# PAPI_M1_Sensor.net
KiCad netlist of a schematic drawn in Altium Designer
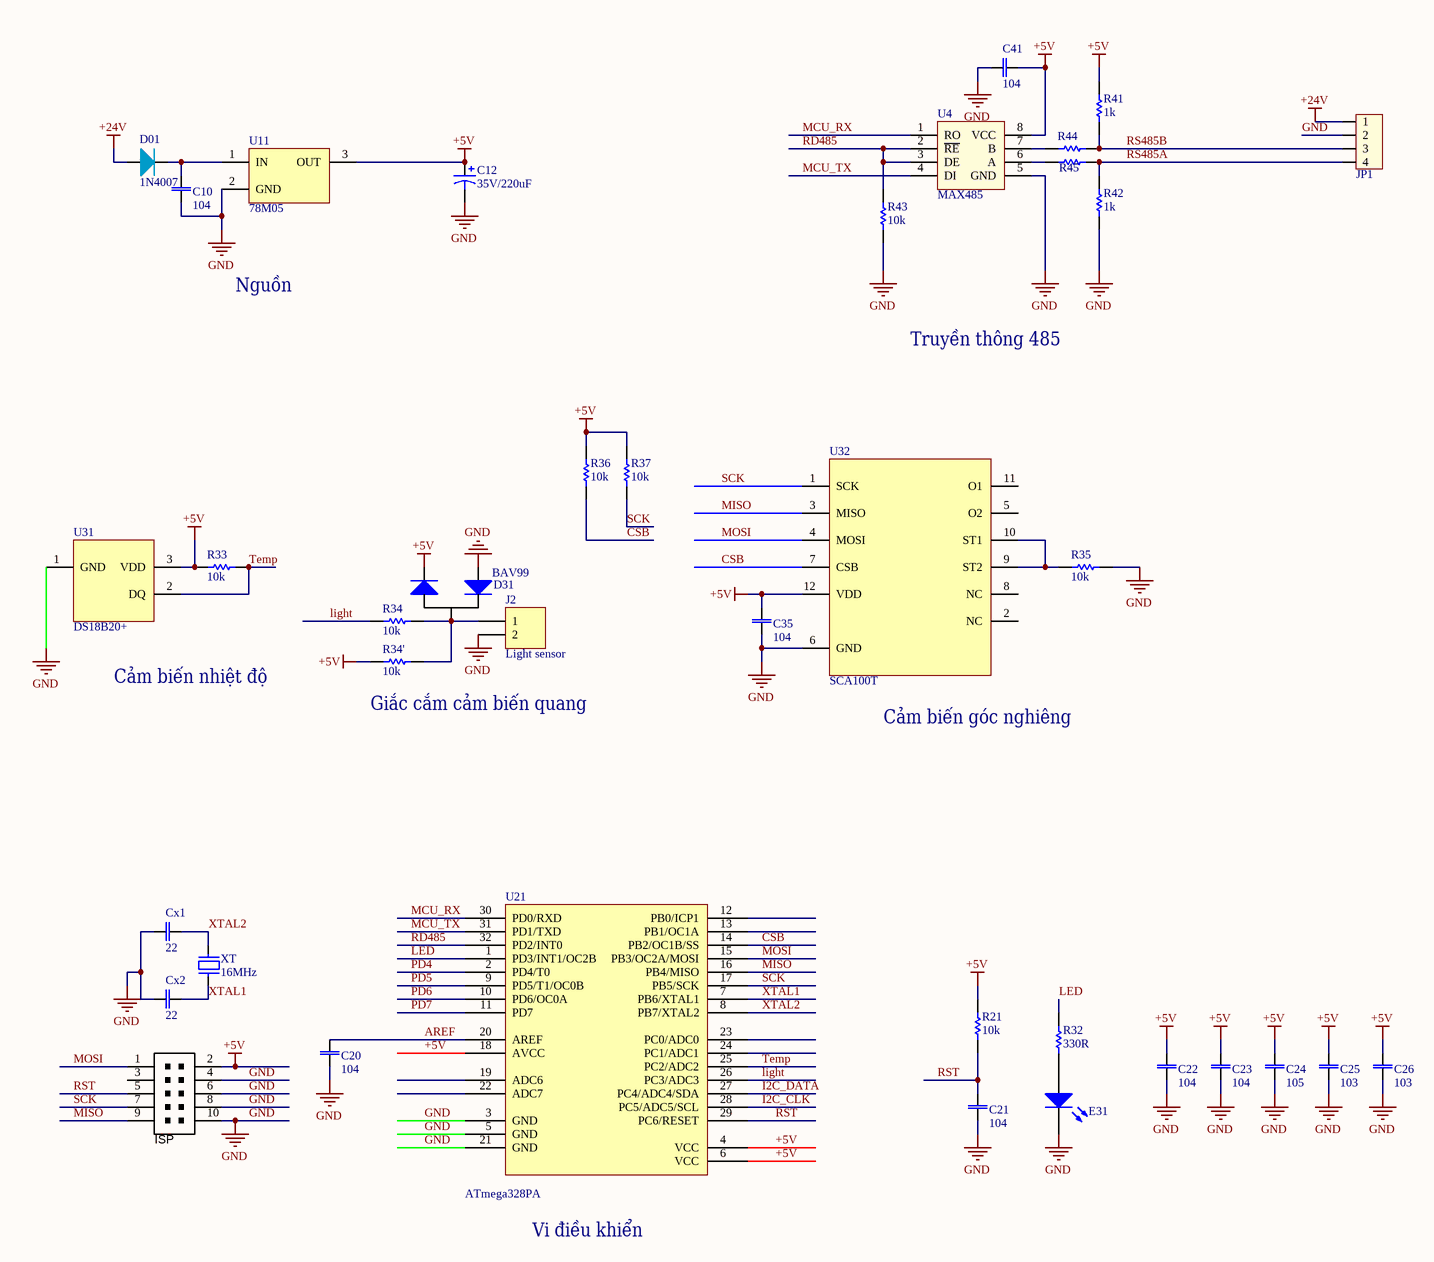
[diagram p0: PAPI_M1_Sensor.SchDoc]

(export (version "E")
  (design (tool "Eeschema 10.0.6"))
  (components
    (comp (ref "C10")
      (value "104")
      (footprint "PBL - SMD Packages:CAPC2012N_F")
      (description "Capacitor non polarized")
      (fields (field (name "Comment") "Tụ điện dán 0805104"))
      (libsource (lib "Tuan") (part "CAP NP"))
    )
    (comp (ref "C12")
      (value "35V/220uF")
      (footprint "CAPE3.5-5.0MM_Rad_10x14mm")
      (fields (field (name "Comment") "Cap"))
      (libsource (lib "Tuan") (part "Cap"))
    )
    (comp (ref "C20")
      (value "104")
      (footprint "PBL - SMD Packages:CAPC2012N_F")
      (description "Capacitor non polarized")
      (fields (field (name "Comment") "Tụ điện dán 0603104"))
      (libsource (lib "Tuan") (part "CAP NP"))
    )
    (comp (ref "C21")
      (value "104")
      (footprint "PBL - SMD Packages:CAPC2012N_F")
      (description "Capacitor non polarized")
      (fields (field (name "Comment") "Tụ điện dán 0603104"))
      (libsource (lib "Tuan") (part "CAP NP"))
    )
    (comp (ref "C22")
      (value "104")
      (footprint "PBL - SMD Packages:CAPC2012N_F")
      (description "Capacitor non polarized")
      (fields (field (name "Comment") "Tụ điện dán 0805104"))
      (libsource (lib "Tuan") (part "CAP NP"))
    )
    (comp (ref "C23")
      (value "104")
      (footprint "PBL - SMD Packages:CAPC2012N_F")
      (description "Capacitor non polarized")
      (fields (field (name "Comment") "Tụ điện dán 0805104"))
      (libsource (lib "Tuan") (part "CAP NP"))
    )
    (comp (ref "C24")
      (value "105")
      (footprint "PBL - SMD Packages:CAPC2012N_F")
      (description "Capacitor non polarized")
      (fields (field (name "Comment") "Tụ điện dán 0805105"))
      (libsource (lib "Tuan") (part "CAP NP"))
    )
    (comp (ref "C25")
      (value "103")
      (footprint "PBL - SMD Packages:CAPC2012N_F")
      (description "Capacitor non polarized")
      (fields (field (name "Comment") "Tụ điện dán 0805103"))
      (libsource (lib "Tuan") (part "CAP NP"))
    )
    (comp (ref "C26")
      (value "103")
      (footprint "PBL - SMD Packages:CAPC2012N_F")
      (description "Capacitor non polarized")
      (fields (field (name "Comment") "Tụ điện dán 0805103"))
      (libsource (lib "Tuan") (part "CAP NP"))
    )
    (comp (ref "C35")
      (value "104")
      (footprint "PBL - SMD Packages:CAPC2012N_F")
      (description "Capacitor non polarized")
      (fields (field (name "Comment") "Tụ điện dán 0805104"))
      (libsource (lib "Tuan") (part "CAP NP"))
    )
    (comp (ref "C41")
      (value "104")
      (footprint "PBL - SMD Packages:CAPC2012N_F")
      (description "Capacitor non polarized")
      (fields (field (name "Comment") "Tụ điện dán 0805104"))
      (libsource (lib "Tuan") (part "CAP NP"))
    )
    (comp (ref "Cx1")
      (value "22")
      (footprint "PBL - SMD Packages:CAPC2012N_F")
      (description "Capacitor non polarized")
      (fields (field (name "Comment") "Tụ điện dán 060322"))
      (libsource (lib "Tuan") (part "CAP NP"))
    )
    (comp (ref "Cx2")
      (value "22")
      (footprint "PBL - SMD Packages:CAPC2012N_F")
      (description "Capacitor non polarized")
      (fields (field (name "Comment") "Tụ điện dán 060322"))
      (libsource (lib "Tuan") (part "CAP NP"))
    )
    (comp (ref "D01")
      (value "Đi ốt cắm1N4007")
      (footprint "swatpcblib:DO-41")
      (fields (field (name "VL1") "1N4007"))
      (libsource (lib "swatpcblib") (part "Diode"))
    )
    (comp (ref "D31")
      (value "BAV99")
      (footprint "SOT323")
      (description "Diode Array 1 Pair Series Connection Standard 70V 215mA (DC) Surface Mount SC-70, SOT-323")
      (libsource (lib "Tuan") (part "BAV99W"))
    )
    (comp (ref "E31") (value "Led") (footprint "LED 5mm Green") (libsource (lib "Tuan") (part "Led")))
    (comp (ref "ISP")
      (value "Giắc đôi 5x2 chân 2.54mm")
      (footprint "10P_PCB_HEADER_BRD_MNT")
      (description "Header THD 10 POS Double-row 2.54mm pitch")
      (libsource (lib "PBL - Connectors") (part "CONN_HEADER_2x5P_0.100in_Male"))
    )
    (comp (ref "J2")
      (value "Light sensor")
      (footprint "heromap:HDR1X2")
      (description "Header, 2-Pin")
      (fields (field (name "PUBLISHER") "Altium Limited"))
      (libsource (lib "heromap") (part "Header 2"))
    )
    (comp (ref "JP1")
      (value "JP4")
      (footprint "heromap:CON4")
      (description "Connector 4")
      (libsource (lib "heromap") (part "Con4"))
    )
    (comp (ref "R21")
      (value "10k")
      (footprint "PBL - SMD Packages:RESC2012N_F")
      (description "Resistor")
      (fields (field (name "Comment") "Điện trở dán 060310k"))
      (libsource (lib "Tuan") (part "Res"))
    )
    (comp (ref "R32")
      (value "330R")
      (footprint "PBL - SMD Packages:RESC2012N_F")
      (description "Resistor")
      (fields (field (name "Comment") "Điện trở dán 0603330R"))
      (libsource (lib "Tuan") (part "Res"))
    )
    (comp (ref "R33")
      (value "10k")
      (footprint "RESC2012N_F")
      (fields (field (name "Comment") "Res_10k_0603"))
      (libsource (lib "Tuan") (part "Res"))
    )
    (comp (ref "R34")
      (value "10k")
      (footprint "RESC2012N_F")
      (fields (field (name "Comment") "Res_10k_0603"))
      (libsource (lib "Tuan") (part "Res"))
    )
    (comp (ref "R34'")
      (value "10k")
      (footprint "RESC2012N_F")
      (fields (field (name "Comment") "Res_10k_0603"))
      (libsource (lib "Tuan") (part "Res"))
    )
    (comp (ref "R35")
      (value "10k")
      (footprint "PBL - SMD Packages:RESC2012N_F")
      (description "Resistor")
      (fields (field (name "Comment") "Điện trở dán 060310k"))
      (libsource (lib "Tuan") (part "Res"))
    )
    (comp (ref "R36")
      (value "10k")
      (footprint "PBL - SMD Packages:RESC2012N_F")
      (description "Resistor")
      (fields (field (name "Comment") "Điện trở dán 060310k"))
      (libsource (lib "Tuan") (part "Res"))
    )
    (comp (ref "R37")
      (value "10k")
      (footprint "PBL - SMD Packages:RESC2012N_F")
      (description "Resistor")
      (fields (field (name "Comment") "Điện trở dán 060310k"))
      (libsource (lib "Tuan") (part "Res"))
    )
    (comp (ref "R41")
      (value "1k")
      (footprint "RESC2012N_F")
      (fields (field (name "Comment") "Res_1k_0603"))
      (libsource (lib "Tuan") (part "Res"))
    )
    (comp (ref "R42")
      (value "1k")
      (footprint "RESC2012N_F")
      (fields (field (name "Comment") "Res_1k_0603"))
      (libsource (lib "Tuan") (part "Res"))
    )
    (comp (ref "R43")
      (value "10k")
      (footprint "RESC2012N_F")
      (fields (field (name "Comment") "Res_10k_0603"))
      (libsource (lib "Tuan") (part "Res"))
    )
    (comp (ref "R44") (value "Res_10R_0805") (footprint "RESC2012N_F") (libsource (lib "Tuan") (part "Res")))
    (comp (ref "R45") (value "Res_10R_0805") (footprint "RESC2012N_F") (libsource (lib "Tuan") (part "Res")))
    (comp (ref "U4")
      (value "MAX485")
      (footprint "SOIC 8")
      (description "RS232 - RS485 (Same sn75176)")
      (libsource (lib "heromap") (part "MAX485"))
    )
    (comp (ref "U11")
      (value "78M05")
      (footprint "TO252 D-PAK")
      (description "Linear Voltage Regulators 5V 500mA Positive")
      (libsource (lib "Tuan") (part "LM78xx"))
    )
    (comp (ref "U21")
      (value "ATmega328PA")
      (footprint "TQFP32")
      (description "ATmega48/168/328")
      (libsource (lib "Tuan") (part "ATmega48/168/328"))
    )
    (comp (ref "U31")
      (value "DS18B20+")
      (footprint "QTO-92")
      (description "SENSOR TEMPERATURE 1-WIRE TO92-3")
      (fields (field (name "DIGI-KEY PART NUMBER") "DS18B20+-ND"))
      (libsource (lib "Tuan") (part "DS18B20"))
    )
    (comp (ref "U32")
      (value "SCA100T")
      (footprint "SCA100T")
      (description "Accelerometer X, Y Axis ±12g 400Hz 12-SMD")
      (libsource (lib "Tuan") (part "SCA100T"))
    )
    (comp (ref "XT") (value "16MHz") (footprint "XT2") (libsource (lib "Tuan") (part "Crystal")))
  )
  (nets
    (net (code "1") (name "+5V") (class "Default")
      (node (ref "C12") (pin "1") (pinfunction "1_1") (pintype "passive"))
      (node (ref "C22") (pin "2") (pinfunction "2_2") (pintype "passive"))
      (node (ref "C23") (pin "2") (pinfunction "2_2") (pintype "passive"))
      (node (ref "C24") (pin "2") (pinfunction "2_2") (pintype "passive"))
      (node (ref "C25") (pin "2") (pinfunction "2_2") (pintype "passive"))
      (node (ref "C26") (pin "2") (pinfunction "2_2") (pintype "passive"))
      (node (ref "C35") (pin "1") (pinfunction "1_1") (pintype "passive"))
      (node (ref "C41") (pin "1") (pinfunction "1_1") (pintype "passive"))
      (node (ref "D31") (pin "2") (pinfunction "K_2") (pintype "passive"))
      (node (ref "ISP") (pin "2") (pinfunction "2_2") (pintype "passive"))
      (node (ref "R21") (pin "2") (pinfunction "2_2") (pintype "passive"))
      (node (ref "R33") (pin "2") (pinfunction "2_2") (pintype "passive"))
      (node (ref "R34'") (pin "2") (pinfunction "2_2") (pintype "passive"))
      (node (ref "R36") (pin "1") (pinfunction "1_1") (pintype "passive"))
      (node (ref "R37") (pin "1") (pinfunction "1_1") (pintype "passive"))
      (node (ref "R41") (pin "2") (pinfunction "2_2") (pintype "passive"))
      (node (ref "U11") (pin "3") (pinfunction "OUT_3") (pintype "passive"))
      (node (ref "U21") (pin "18") (pinfunction "AVCC_18") (pintype "passive"))
      (node (ref "U21") (pin "4") (pinfunction "VCC_4") (pintype "passive"))
      (node (ref "U21") (pin "6") (pinfunction "VCC_6") (pintype "passive"))
      (node (ref "U31") (pin "3") (pinfunction "VDD_3") (pintype "passive"))
      (node (ref "U32") (pin "12") (pinfunction "VDD_12") (pintype "passive"))
      (node (ref "U4") (pin "8") (pinfunction "VCC_8") (pintype "passive"))
    )
    (net (code "2") (name "+24V") (class "Default")
      (node (ref "D01") (pin "A") (pinfunction "A_A") (pintype "passive"))
      (node (ref "JP1") (pin "1") (pinfunction "1_1") (pintype "passive"))
    )
    (net (code "3") (name "/AREF") (class "Default")
      (node (ref "C20") (pin "2") (pinfunction "2_2") (pintype "passive"))
      (node (ref "U21") (pin "20") (pinfunction "AREF_20") (pintype "passive"))
    )
    (net (code "4") (name "/CSB") (class "Default")
      (node (ref "R36") (pin "2") (pinfunction "2_2") (pintype "passive"))
      (node (ref "U21") (pin "14") (pinfunction "PB2/OC1B/SS_14") (pintype "passive"))
      (node (ref "U32") (pin "7") (pinfunction "CSB_7") (pintype "passive"))
    )
    (net (code "5") (name "/I2C_CLK") (class "Default")
      (node (ref "U21") (pin "28") (pinfunction "PC5/ADC5/SCL_28") (pintype "passive"))
    )
    (net (code "6") (name "/I2C_DATA") (class "Default")
      (node (ref "U21") (pin "27") (pinfunction "PC4/ADC4/SDA_27") (pintype "passive"))
    )
    (net (code "7") (name "/LED") (class "Default")
      (node (ref "R32") (pin "1") (pinfunction "1_1") (pintype "passive"))
      (node (ref "U21") (pin "1") (pinfunction "PD3/INT1/OC2B_1") (pintype "passive"))
    )
    (net (code "8") (name "/MCU_RX") (class "Default")
      (node (ref "U21") (pin "30") (pinfunction "PD0/RXD_30") (pintype "passive"))
      (node (ref "U4") (pin "1") (pinfunction "RO_1") (pintype "passive"))
    )
    (net (code "9") (name "/MCU_TX") (class "Default")
      (node (ref "U21") (pin "31") (pinfunction "PD1/TXD_31") (pintype "passive"))
      (node (ref "U4") (pin "4") (pinfunction "DI_4") (pintype "passive"))
    )
    (net (code "10") (name "/MISO") (class "Default")
      (node (ref "ISP") (pin "9") (pinfunction "9_9") (pintype "passive"))
      (node (ref "U21") (pin "16") (pinfunction "PB4/MISO_16") (pintype "passive"))
      (node (ref "U32") (pin "3") (pinfunction "MISO_3") (pintype "passive"))
    )
    (net (code "11") (name "/MOSI") (class "Default")
      (node (ref "ISP") (pin "1") (pinfunction "1_1") (pintype "passive"))
      (node (ref "U21") (pin "15") (pinfunction "PB3/OC2A/MOSI_15") (pintype "passive"))
      (node (ref "U32") (pin "4") (pinfunction "MOSI_4") (pintype "passive"))
    )
    (net (code "12") (name "/PD4") (class "Default")
      (node (ref "U21") (pin "2") (pinfunction "PD4/T0_2") (pintype "passive"))
    )
    (net (code "13") (name "/PD5") (class "Default")
      (node (ref "U21") (pin "9") (pinfunction "PD5/T1/OC0B_9") (pintype "passive"))
    )
    (net (code "14") (name "/PD6") (class "Default")
      (node (ref "U21") (pin "10") (pinfunction "PD6/OC0A_10") (pintype "passive"))
    )
    (net (code "15") (name "/PD7") (class "Default")
      (node (ref "U21") (pin "11") (pinfunction "PD7_11") (pintype "passive"))
    )
    (net (code "16") (name "/RD485") (class "Default")
      (node (ref "R43") (pin "2") (pinfunction "2_2") (pintype "passive"))
      (node (ref "U21") (pin "32") (pinfunction "PD2/INT0_32") (pintype "passive"))
      (node (ref "U4") (pin "2") (pinfunction "~{RE}_2") (pintype "passive"))
      (node (ref "U4") (pin "3") (pinfunction "DE_3") (pintype "passive"))
    )
    (net (code "17") (name "/RS485A") (class "Default")
      (node (ref "JP1") (pin "4") (pinfunction "4_4") (pintype "passive"))
      (node (ref "R42") (pin "2") (pinfunction "2_2") (pintype "passive"))
      (node (ref "R45") (pin "2") (pinfunction "2_2") (pintype "passive"))
    )
    (net (code "18") (name "/RS485B") (class "Default")
      (node (ref "JP1") (pin "3") (pinfunction "3_3") (pintype "passive"))
      (node (ref "R41") (pin "1") (pinfunction "1_1") (pintype "passive"))
      (node (ref "R44") (pin "2") (pinfunction "2_2") (pintype "passive"))
    )
    (net (code "19") (name "/RST") (class "Default")
      (node (ref "C21") (pin "2") (pinfunction "2_2") (pintype "passive"))
      (node (ref "ISP") (pin "5") (pinfunction "5_5") (pintype "passive"))
      (node (ref "R21") (pin "1") (pinfunction "1_1") (pintype "passive"))
      (node (ref "U21") (pin "29") (pinfunction "PC6/RESET_29") (pintype "passive"))
    )
    (net (code "20") (name "/SCK") (class "Default")
      (node (ref "ISP") (pin "7") (pinfunction "7_7") (pintype "passive"))
      (node (ref "R37") (pin "2") (pinfunction "2_2") (pintype "passive"))
      (node (ref "U21") (pin "17") (pinfunction "PB5/SCK_17") (pintype "passive"))
      (node (ref "U32") (pin "1") (pinfunction "SCK_1") (pintype "passive"))
    )
    (net (code "21") (name "/Temp") (class "Default")
      (node (ref "R33") (pin "1") (pinfunction "1_1") (pintype "passive"))
      (node (ref "U21") (pin "25") (pinfunction "PC2/ADC2_25") (pintype "passive"))
      (node (ref "U31") (pin "2") (pinfunction "DQ_2") (pintype "passive"))
    )
    (net (code "22") (name "/XTAL1") (class "Default")
      (node (ref "Cx2") (pin "1") (pinfunction "1_1") (pintype "passive"))
      (node (ref "U21") (pin "7") (pinfunction "PB6/XTAL1_7") (pintype "passive"))
      (node (ref "XT") (pin "1") (pinfunction "1_1") (pintype "passive"))
    )
    (net (code "23") (name "/XTAL2") (class "Default")
      (node (ref "Cx1") (pin "1") (pinfunction "1_1") (pintype "passive"))
      (node (ref "U21") (pin "8") (pinfunction "PB7/XTAL2_8") (pintype "passive"))
      (node (ref "XT") (pin "2") (pinfunction "2_2") (pintype "passive"))
    )
    (net (code "24") (name "/light") (class "Default")
      (node (ref "R34") (pin "1") (pinfunction "1_1") (pintype "passive"))
      (node (ref "U21") (pin "26") (pinfunction "PC3/ADC3_26") (pintype "passive"))
    )
    (net (code "25") (name "GND") (class "Default")
      (node (ref "C10") (pin "1") (pinfunction "1_1") (pintype "passive"))
      (node (ref "C12") (pin "2") (pinfunction "2_2") (pintype "passive"))
      (node (ref "C20") (pin "1") (pinfunction "1_1") (pintype "passive"))
      (node (ref "C21") (pin "1") (pinfunction "1_1") (pintype "passive"))
      (node (ref "C22") (pin "1") (pinfunction "1_1") (pintype "passive"))
      (node (ref "C23") (pin "1") (pinfunction "1_1") (pintype "passive"))
      (node (ref "C24") (pin "1") (pinfunction "1_1") (pintype "passive"))
      (node (ref "C25") (pin "1") (pinfunction "1_1") (pintype "passive"))
      (node (ref "C26") (pin "1") (pinfunction "1_1") (pintype "passive"))
      (node (ref "C35") (pin "2") (pinfunction "2_2") (pintype "passive"))
      (node (ref "C41") (pin "2") (pinfunction "2_2") (pintype "passive"))
      (node (ref "Cx1") (pin "2") (pinfunction "2_2") (pintype "passive"))
      (node (ref "Cx2") (pin "2") (pinfunction "2_2") (pintype "passive"))
      (node (ref "D31") (pin "1") (pinfunction "A_1") (pintype "passive"))
      (node (ref "E31") (pin "2") (pinfunction "K_2") (pintype "passive"))
      (node (ref "ISP") (pin "10") (pinfunction "10_10") (pintype "passive"))
      (node (ref "ISP") (pin "4") (pinfunction "4_4") (pintype "passive"))
      (node (ref "ISP") (pin "6") (pinfunction "6_6") (pintype "passive"))
      (node (ref "ISP") (pin "8") (pinfunction "8_8") (pintype "passive"))
      (node (ref "J2") (pin "2") (pinfunction "2_2") (pintype "passive"))
      (node (ref "JP1") (pin "2") (pinfunction "2_2") (pintype "passive"))
      (node (ref "R35") (pin "1") (pinfunction "1_1") (pintype "passive"))
      (node (ref "R42") (pin "1") (pinfunction "1_1") (pintype "passive"))
      (node (ref "R43") (pin "1") (pinfunction "1_1") (pintype "passive"))
      (node (ref "U11") (pin "2") (pinfunction "GND_2") (pintype "passive"))
      (node (ref "U21") (pin "21") (pinfunction "GND_21") (pintype "power_in"))
      (node (ref "U21") (pin "3") (pinfunction "GND_3") (pintype "power_in"))
      (node (ref "U21") (pin "5") (pinfunction "GND_5") (pintype "power_in"))
      (node (ref "U31") (pin "1") (pinfunction "GND_1") (pintype "passive"))
      (node (ref "U32") (pin "6") (pinfunction "GND_6") (pintype "passive"))
      (node (ref "U4") (pin "5") (pinfunction "GND_5") (pintype "passive"))
    )
    (net (code "26") (name "Net-(D31-AK)") (class "Default")
      (node (ref "D31") (pin "3") (pinfunction "AK_3") (pintype "passive"))
      (node (ref "J2") (pin "1") (pinfunction "1_1") (pintype "passive"))
      (node (ref "R34") (pin "2") (pinfunction "2_2") (pintype "passive"))
      (node (ref "R34'") (pin "1") (pinfunction "1_1") (pintype "passive"))
    )
    (net (code "27") (name "Net-(E31-A)") (class "Default")
      (node (ref "E31") (pin "1") (pinfunction "A_1") (pintype "passive"))
      (node (ref "R32") (pin "2") (pinfunction "2_2") (pintype "passive"))
    )
    (net (code "28") (name "Net-(U4-A)") (class "Default")
      (node (ref "R45") (pin "1") (pinfunction "1_1") (pintype "passive"))
      (node (ref "U4") (pin "6") (pinfunction "A_6") (pintype "passive"))
    )
    (net (code "29") (name "Net-(U4-B)") (class "Default")
      (node (ref "R44") (pin "1") (pinfunction "1_1") (pintype "passive"))
      (node (ref "U4") (pin "7") (pinfunction "B_7") (pintype "passive"))
    )
    (net (code "30") (name "Net-(U11-IN)") (class "Default")
      (node (ref "C10") (pin "2") (pinfunction "2_2") (pintype "passive"))
      (node (ref "D01") (pin "K") (pinfunction "K_K") (pintype "passive"))
      (node (ref "U11") (pin "1") (pinfunction "IN_1") (pintype "passive"))
    )
    (net (code "31") (name "Net-(U32-ST1)") (class "Default")
      (node (ref "R35") (pin "2") (pinfunction "2_2") (pintype "passive"))
      (node (ref "U32") (pin "10") (pinfunction "ST1_10") (pintype "passive"))
      (node (ref "U32") (pin "9") (pinfunction "ST2_9") (pintype "passive"))
    )
    (net (code "32") (name "unconnected-(ISP-Pad3)") (class "Default")
      (node (ref "ISP") (pin "3") (pinfunction "3_3") (pintype "passive"))
    )
    (net (code "33") (name "unconnected-(U21-ADC6-Pad19)") (class "Default")
      (node (ref "U21") (pin "19") (pinfunction "ADC6_19") (pintype "passive"))
    )
    (net (code "34") (name "unconnected-(U21-ADC7-Pad22)") (class "Default")
      (node (ref "U21") (pin "22") (pinfunction "ADC7_22") (pintype "passive"))
    )
    (net (code "35") (name "unconnected-(U21-PB0{slash}ICP1-Pad12)") (class "Default")
      (node (ref "U21") (pin "12") (pinfunction "PB0/ICP1_12") (pintype "passive"))
    )
    (net (code "36") (name "unconnected-(U21-PB1{slash}OC1A-Pad13)") (class "Default")
      (node (ref "U21") (pin "13") (pinfunction "PB1/OC1A_13") (pintype "passive"))
    )
    (net (code "37") (name "unconnected-(U21-PC0{slash}ADC0-Pad23)") (class "Default")
      (node (ref "U21") (pin "23") (pinfunction "PC0/ADC0_23") (pintype "passive"))
    )
    (net (code "38") (name "unconnected-(U21-PC1{slash}ADC1-Pad24)") (class "Default")
      (node (ref "U21") (pin "24") (pinfunction "PC1/ADC1_24") (pintype "passive"))
    )
    (net (code "39") (name "unconnected-(U32-NC-Pad2)") (class "Default")
      (node (ref "U32") (pin "2") (pinfunction "NC_2") (pintype "passive"))
    )
    (net (code "40") (name "unconnected-(U32-NC-Pad8)") (class "Default")
      (node (ref "U32") (pin "8") (pinfunction "NC_8") (pintype "passive"))
    )
    (net (code "41") (name "unconnected-(U32-O1-Pad11)") (class "Default")
      (node (ref "U32") (pin "11") (pinfunction "O1_11") (pintype "passive"))
    )
    (net (code "42") (name "unconnected-(U32-O2-Pad5)") (class "Default")
      (node (ref "U32") (pin "5") (pinfunction "O2_5") (pintype "passive"))
    )
  )
)
